# LevelShifter.net
KiCad netlist of a schematic drawn in Altium Designer
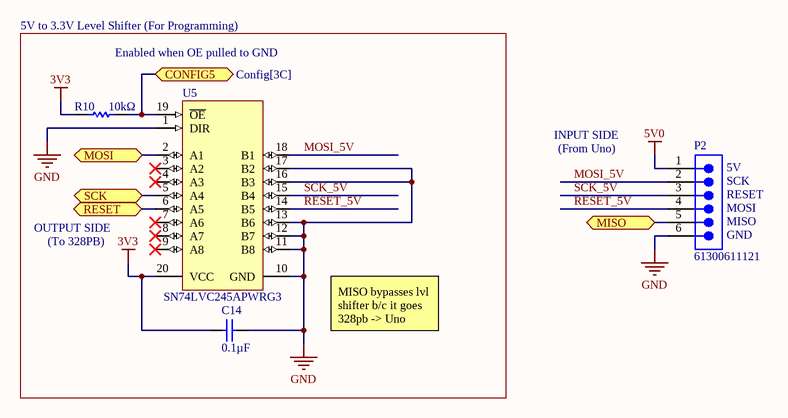
[diagram p0: LevelShifter.SchDoc]

(export (version "E")
  (design (tool "Eeschema 10.0.6"))
  (components
    (comp (ref "C14")
      (value "0.1µF")
      (footprint "CAPC3216X100X50LL20T25")
      (description "Chip Capacitor, 100 nF, +/- 10%, 25 V, -55 to 125 degC, 1206 (3216 Metric), RoHS, Tape and Reel")
      (fields (field (name "MANUFACTURER") "Kemet"))
      (libsource (lib "Altium Content Vault") (part "CAP-NP-2"))
    )
    (comp (ref "P2")
      (value "61300611121")
      (footprint "61300611121")
      (libsource (lib "Altium Content Vault") (part "Header_Male_1R_06P"))
    )
    (comp (ref "R10")
      (value "10kΩ")
      (footprint "RESC3116X65X40LL10T20")
      (description "Chip Resistor, 10 KOhm, +/- 1%, 0.25 W, -55 to 155 degC, 1206 (3216 Metric), RoHS, Tape and Reel")
      (fields (field (name "TOLERANCE") "1%") (field (name "MANUFACTURER") "Yageo"))
      (libsource (lib "Altium Content Vault") (part "RES-2"))
    )
    (comp (ref "U5")
      (value "SN74LVC245APWRG3")
      (footprint "PW0020A_N")
      (description "Octal Bus Transceiver With 3-State Outputs, PW0020A, LARGE T&R")
      (fields
        (field (name "MANUFACTURER") "Texas Instruments")
        (field (name "GENERIC PART NUMBER") "SN74LVC245A")
      )
      (libsource (lib "Altium Content Vault") (part "TI-SN_CDX4XXXXXX245XX_6XXX-20"))
    )
  )
  (nets
    (net (code "1") (name "/CONFIG5") (class "Default")
      (node (ref "R10") (pin "1") (pinfunction "1_1") (pintype "passive"))
      (node (ref "U5") (pin "19") (pinfunction "~{OE}_19") (pintype "input"))
    )
    (net (code "2") (name "/MISO") (class "Default")
      (node (ref "P2") (pin "5") (pinfunction "5_5") (pintype "passive"))
    )
    (net (code "3") (name "/MOSI") (class "Default")
      (node (ref "U5") (pin "2") (pinfunction "A1_2") (pintype "bidirectional"))
    )
    (net (code "4") (name "/MOSI_5V") (class "Default")
      (node (ref "P2") (pin "2") (pinfunction "2_2") (pintype "passive"))
      (node (ref "U5") (pin "18") (pinfunction "B1_18") (pintype "bidirectional"))
    )
    (net (code "5") (name "/RESET") (class "Default")
      (node (ref "U5") (pin "6") (pinfunction "A5_6") (pintype "bidirectional"))
    )
    (net (code "6") (name "/RESET_5V") (class "Default")
      (node (ref "P2") (pin "4") (pinfunction "4_4") (pintype "passive"))
      (node (ref "U5") (pin "14") (pinfunction "B5_14") (pintype "bidirectional"))
    )
    (net (code "7") (name "/SCK") (class "Default")
      (node (ref "U5") (pin "5") (pinfunction "A4_5") (pintype "bidirectional"))
    )
    (net (code "8") (name "/SCK_5V") (class "Default")
      (node (ref "P2") (pin "3") (pinfunction "3_3") (pintype "passive"))
      (node (ref "U5") (pin "15") (pinfunction "B4_15") (pintype "bidirectional"))
    )
    (net (code "9") (name "3V3") (class "Default")
      (node (ref "C14") (pin "1") (pinfunction "1_1") (pintype "passive"))
      (node (ref "R10") (pin "2") (pinfunction "2_2") (pintype "passive"))
      (node (ref "U5") (pin "20") (pinfunction "VCC_20") (pintype "power_in"))
    )
    (net (code "10") (name "5V0") (class "Default")
      (node (ref "P2") (pin "1") (pinfunction "1_1") (pintype "passive"))
    )
    (net (code "11") (name "GND") (class "Default")
      (node (ref "C14") (pin "2") (pinfunction "2_2") (pintype "passive"))
      (node (ref "P2") (pin "6") (pinfunction "6_6") (pintype "passive"))
      (node (ref "U5") (pin "1") (pinfunction "DIR_1") (pintype "input"))
      (node (ref "U5") (pin "10") (pinfunction "GND_10") (pintype "power_in"))
      (node (ref "U5") (pin "11") (pinfunction "B8_11") (pintype "bidirectional"))
      (node (ref "U5") (pin "12") (pinfunction "B7_12") (pintype "bidirectional"))
      (node (ref "U5") (pin "13") (pinfunction "B6_13") (pintype "bidirectional"))
      (node (ref "U5") (pin "16") (pinfunction "B3_16") (pintype "bidirectional"))
      (node (ref "U5") (pin "17") (pinfunction "B2_17") (pintype "bidirectional"))
    )
    (net (code "12") (name "unconnected-(U5-A2-Pad3)") (class "Default")
      (node (ref "U5") (pin "3") (pinfunction "A2_3") (pintype "bidirectional+no_connect"))
    )
    (net (code "13") (name "unconnected-(U5-A3-Pad4)") (class "Default")
      (node (ref "U5") (pin "4") (pinfunction "A3_4") (pintype "bidirectional+no_connect"))
    )
    (net (code "14") (name "unconnected-(U5-A6-Pad7)") (class "Default")
      (node (ref "U5") (pin "7") (pinfunction "A6_7") (pintype "bidirectional+no_connect"))
    )
    (net (code "15") (name "unconnected-(U5-A7-Pad8)") (class "Default")
      (node (ref "U5") (pin "8") (pinfunction "A7_8") (pintype "bidirectional+no_connect"))
    )
    (net (code "16") (name "unconnected-(U5-A8-Pad9)") (class "Default")
      (node (ref "U5") (pin "9") (pinfunction "A8_9") (pintype "bidirectional+no_connect"))
    )
  )
)
